# fishnet-0_1.net
KiCad netlist of a schematic drawn in EAGLE
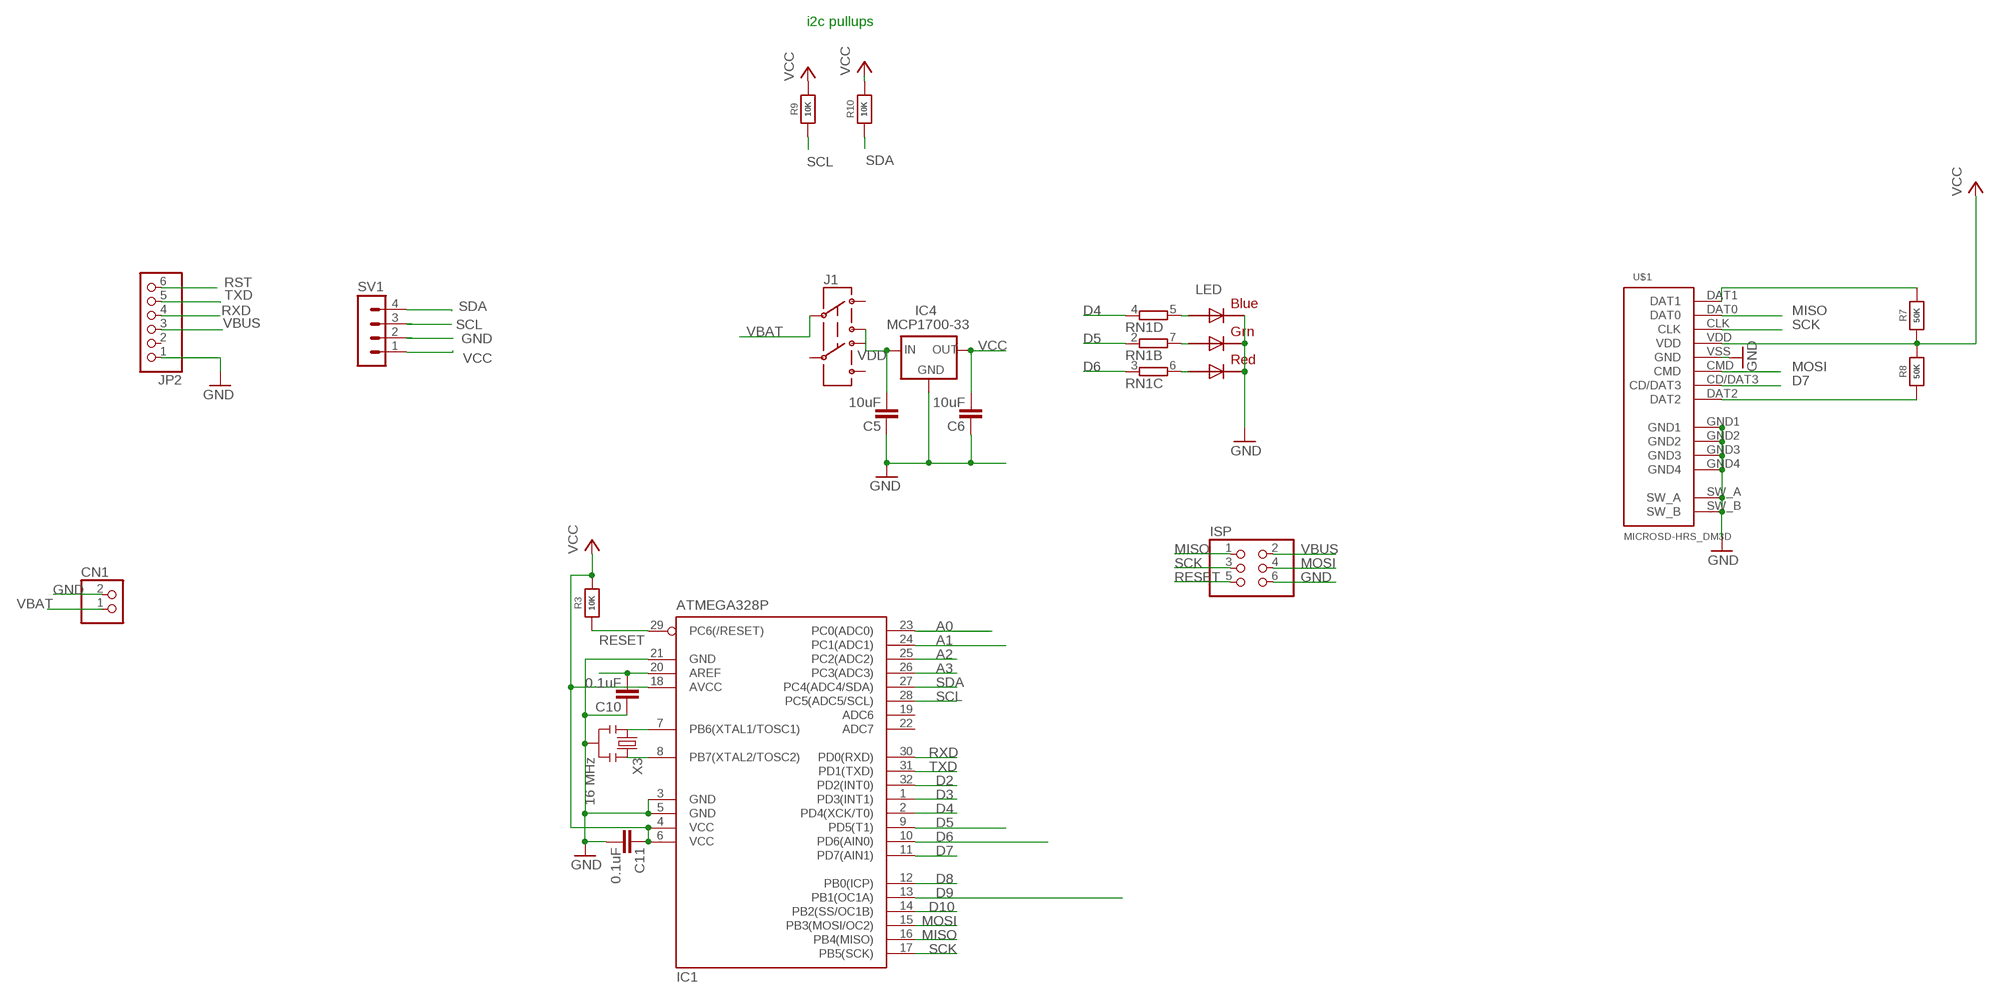
[diagram p0: schematic, sheet 1]

(export (version "E")
  (design (tool "Eeschema 10.0.6"))
  (components
    (comp (ref "C5")
      (value "10uF")
      (footprint "eagle-import:0603-CAP")
      (libsource (lib "eagle-import") (part "CAP0603-CAP"))
    )
    (comp (ref "C6")
      (value "10uF")
      (footprint "eagle-import:0603-CAP")
      (libsource (lib "eagle-import") (part "CAP0603-CAP"))
    )
    (comp (ref "C10")
      (value "0.1uF")
      (footprint "eagle-import:0603-CAP")
      (libsource (lib "eagle-import") (part "CAP0603-CAP"))
    )
    (comp (ref "C11")
      (value "0.1uF")
      (footprint "eagle-import:0603-CAP")
      (libsource (lib "eagle-import") (part "CAP0603-CAP"))
    )
    (comp (ref "CN1")
      (value "JST_2PIN-SMT-RA")
      (footprint "eagle-import:JST-PH-2-SMT-RA")
      (libsource (lib "eagle-import") (part "JST_2PIN-SMT-RA"))
    )
    (comp (ref "IC1")
      (value "ATMEGA328P")
      (footprint "eagle-import:TQFP32-08")
      (fields (field (name "MPN") "ATMEGA8-16AU"))
      (libsource (lib "eagle-import") (part "MEGA8-AI"))
    )
    (comp (ref "IC4")
      (value "MCP1700-33")
      (footprint "eagle-import:SOT89")
      (libsource (lib "eagle-import") (part "MCP1700SOT89"))
    )
    (comp (ref "ISP")
      (value "PINHD-2X3")
      (footprint "eagle-import:2X03")
      (libsource (lib "eagle-import") (part "PINHD-2X3"))
    )
    (comp (ref "J1")
      (value "AYZ0202")
      (footprint "eagle-import:AYZ0202")
      (libsource (lib "eagle-import") (part "AYZ0202"))
    )
    (comp (ref "JP2")
      (value "PINHD-1X6")
      (footprint "eagle-import:1X06")
      (libsource (lib "eagle-import") (part "PINHD-1X6"))
    )
    (comp (ref "LED")
      (value "RGBLED5050")
      (footprint "eagle-import:RGBLED5050")
      (libsource (lib "eagle-import") (part "RGBLED5050"))
    )
    (comp (ref "R3")
      (value "10K")
      (footprint "eagle-import:0603-NO")
      (libsource (lib "eagle-import") (part "RESISTOR_0603_NOOUT"))
    )
    (comp (ref "R7")
      (value "50K")
      (footprint "eagle-import:0603-NO")
      (libsource (lib "eagle-import") (part "RESISTOR_0603_NOOUT"))
    )
    (comp (ref "R8")
      (value "50K")
      (footprint "eagle-import:0603-NO")
      (libsource (lib "eagle-import") (part "RESISTOR_0603_NOOUT"))
    )
    (comp (ref "R9")
      (value "10K")
      (footprint "eagle-import:0603-NO")
      (libsource (lib "eagle-import") (part "RESISTOR_0603_NOOUT"))
    )
    (comp (ref "R10")
      (value "10K")
      (footprint "eagle-import:0603-NO")
      (libsource (lib "eagle-import") (part "RESISTOR_0603_NOOUT"))
    )
    (comp (ref "RN1")
      (value "4R-NEXB38V")
      (footprint "eagle-import:EXB38V")
      (libsource (lib "eagle-import") (part "4R-NEXB38V"))
    )
    (comp (ref "SV1")
      (value "MA04-1")
      (footprint "eagle-import:MA04-1")
      (libsource (lib "eagle-import") (part "MA04-1"))
    )
    (comp (ref "U$1")
      (value "MICROSD-HRS_DM3D")
      (footprint "eagle-import:DM3D")
      (libsource (lib "eagle-import") (part "MICROSD-HRS_DM3D"))
    )
    (comp (ref "X3")
      (value "16 MHz")
      (footprint "eagle-import:RESONATOR-SMD")
      (libsource (lib "eagle-import") (part "RESONATORSMD"))
    )
  )
  (nets
    (net (code "1") (name "/A0") (class "Default")
      (node (ref "IC1") (pin "23") (pinfunction "PC0(ADC0)_23") (pintype "bidirectional"))
    )
    (net (code "2") (name "/A1") (class "Default")
      (node (ref "IC1") (pin "24") (pinfunction "PC1(ADC1)_24") (pintype "bidirectional"))
    )
    (net (code "3") (name "/A2") (class "Default")
      (node (ref "IC1") (pin "25") (pinfunction "PC2(ADC2)_25") (pintype "bidirectional"))
    )
    (net (code "4") (name "/A3") (class "Default")
      (node (ref "IC1") (pin "26") (pinfunction "PC3(ADC3)_26") (pintype "bidirectional"))
    )
    (net (code "5") (name "/D2") (class "Default")
      (node (ref "IC1") (pin "32") (pinfunction "PD2(INT0)_32") (pintype "bidirectional"))
    )
    (net (code "6") (name "/D3") (class "Default")
      (node (ref "IC1") (pin "1") (pinfunction "PD3(INT1)_1") (pintype "bidirectional"))
    )
    (net (code "7") (name "/D4") (class "Default")
      (node (ref "IC1") (pin "2") (pinfunction "PD4(XCK/T0)_2") (pintype "bidirectional"))
      (node (ref "RN1") (pin "4") (pinfunction "1_4") (pintype "passive"))
    )
    (net (code "8") (name "/D5") (class "Default")
      (node (ref "IC1") (pin "9") (pinfunction "PD5(T1)_9") (pintype "bidirectional"))
      (node (ref "RN1") (pin "2") (pinfunction "1_2") (pintype "passive"))
    )
    (net (code "9") (name "/D6") (class "Default")
      (node (ref "IC1") (pin "10") (pinfunction "PD6(AIN0)_10") (pintype "bidirectional"))
      (node (ref "RN1") (pin "3") (pinfunction "1_3") (pintype "passive"))
    )
    (net (code "10") (name "/D7") (class "Default")
      (node (ref "IC1") (pin "11") (pinfunction "PD7(AIN1)_11") (pintype "bidirectional"))
      (node (ref "U$1") (pin "CD/DAT3") (pinfunction "CD/DAT3_CD/DAT3") (pintype "bidirectional"))
    )
    (net (code "11") (name "/D8") (class "Default")
      (node (ref "IC1") (pin "12") (pinfunction "PB0(ICP)_12") (pintype "bidirectional"))
    )
    (net (code "12") (name "/D9") (class "Default")
      (node (ref "IC1") (pin "13") (pinfunction "PB1(OC1A)_13") (pintype "bidirectional"))
    )
    (net (code "13") (name "/D10") (class "Default")
      (node (ref "IC1") (pin "14") (pinfunction "PB2(SS/OC1B)_14") (pintype "bidirectional"))
    )
    (net (code "14") (name "/MISO") (class "Default")
      (node (ref "IC1") (pin "16") (pinfunction "PB4(MISO)_16") (pintype "bidirectional"))
      (node (ref "ISP") (pin "1") (pinfunction "1_1") (pintype "passive"))
      (node (ref "U$1") (pin "DAT0") (pinfunction "DAT0_DAT0") (pintype "bidirectional"))
    )
    (net (code "15") (name "/MOSI") (class "Default")
      (node (ref "IC1") (pin "15") (pinfunction "PB3(MOSI/OC2)_15") (pintype "bidirectional"))
      (node (ref "ISP") (pin "4") (pinfunction "4_4") (pintype "passive"))
      (node (ref "U$1") (pin "CMD") (pinfunction "CMD_CMD") (pintype "bidirectional"))
    )
    (net (code "16") (name "/RESET") (class "Default")
      (node (ref "IC1") (pin "29") (pinfunction "PC6(/RESET)_29") (pintype "bidirectional"))
      (node (ref "ISP") (pin "5") (pinfunction "5_5") (pintype "passive"))
      (node (ref "R3") (pin "1") (pinfunction "1_1") (pintype "passive"))
    )
    (net (code "17") (name "/RST") (class "Default")
      (node (ref "JP2") (pin "6") (pinfunction "6_6") (pintype "passive"))
    )
    (net (code "18") (name "/RXD") (class "Default")
      (node (ref "IC1") (pin "30") (pinfunction "PD0(RXD)_30") (pintype "bidirectional"))
      (node (ref "JP2") (pin "4") (pinfunction "4_4") (pintype "passive"))
    )
    (net (code "19") (name "/SCK") (class "Default")
      (node (ref "IC1") (pin "17") (pinfunction "PB5(SCK)_17") (pintype "bidirectional"))
      (node (ref "ISP") (pin "3") (pinfunction "3_3") (pintype "passive"))
      (node (ref "U$1") (pin "CLK") (pinfunction "CLK_CLK") (pintype "bidirectional"))
    )
    (net (code "20") (name "/SCL") (class "Default")
      (node (ref "IC1") (pin "28") (pinfunction "PC5(ADC5/SCL)_28") (pintype "bidirectional"))
      (node (ref "R9") (pin "1") (pinfunction "1_1") (pintype "passive"))
      (node (ref "SV1") (pin "3") (pinfunction "3_3") (pintype "passive"))
    )
    (net (code "21") (name "/SDA") (class "Default")
      (node (ref "IC1") (pin "27") (pinfunction "PC4(ADC4/SDA)_27") (pintype "bidirectional"))
      (node (ref "R10") (pin "1") (pinfunction "1_1") (pintype "passive"))
      (node (ref "SV1") (pin "4") (pinfunction "4_4") (pintype "passive"))
    )
    (net (code "22") (name "/TXD") (class "Default")
      (node (ref "IC1") (pin "31") (pinfunction "PD1(TXD)_31") (pintype "bidirectional"))
      (node (ref "JP2") (pin "5") (pinfunction "5_5") (pintype "passive"))
    )
    (net (code "23") (name "/VBAT") (class "Default")
      (node (ref "CN1") (pin "1") (pinfunction "2_1") (pintype "passive"))
      (node (ref "J1") (pin "2") (pinfunction "2_2") (pintype "bidirectional"))
    )
    (net (code "24") (name "/VBUS") (class "Default")
      (node (ref "ISP") (pin "2") (pinfunction "2_2") (pintype "passive"))
      (node (ref "JP2") (pin "3") (pinfunction "3_3") (pintype "passive"))
    )
    (net (code "25") (name "/VDD") (class "Default")
      (node (ref "C5") (pin "1") (pinfunction "1_1") (pintype "passive"))
      (node (ref "IC4") (pin "2") (pinfunction "IN_2") (pintype "input"))
      (node (ref "J1") (pin "1") (pinfunction "3_1") (pintype "bidirectional"))
    )
    (net (code "26") (name "GND") (class "Default")
      (node (ref "C10") (pin "2") (pinfunction "2_2") (pintype "passive"))
      (node (ref "C11") (pin "1") (pinfunction "1_1") (pintype "passive"))
      (node (ref "C5") (pin "2") (pinfunction "2_2") (pintype "passive"))
      (node (ref "C6") (pin "2") (pinfunction "2_2") (pintype "passive"))
      (node (ref "CN1") (pin "2") (pinfunction "1_2") (pintype "passive"))
      (node (ref "IC1") (pin "21") (pinfunction "GND_21") (pintype "power_in"))
      (node (ref "IC1") (pin "3") (pinfunction "GND_3") (pintype "power_in"))
      (node (ref "IC1") (pin "5") (pinfunction "GND_5") (pintype "power_in"))
      (node (ref "IC4") (pin "1") (pinfunction "GND_1") (pintype "input"))
      (node (ref "ISP") (pin "6") (pinfunction "6_6") (pintype "passive"))
      (node (ref "JP2") (pin "1") (pinfunction "1_1") (pintype "passive"))
      (node (ref "LED") (pin "4") (pinfunction "BLUE_C_4") (pintype "bidirectional"))
      (node (ref "LED") (pin "5") (pinfunction "RED_C_5") (pintype "bidirectional"))
      (node (ref "LED") (pin "6") (pinfunction "GREEN_C_6") (pintype "bidirectional"))
      (node (ref "SV1") (pin "2") (pinfunction "2_2") (pintype "passive"))
      (node (ref "U$1") (pin "GND1") (pinfunction "GND1_GND1") (pintype "bidirectional"))
      (node (ref "U$1") (pin "GND2") (pinfunction "GND2_GND2") (pintype "bidirectional"))
      (node (ref "U$1") (pin "GND3") (pinfunction "GND3_GND3") (pintype "bidirectional"))
      (node (ref "U$1") (pin "GND4") (pinfunction "GND4_GND4") (pintype "bidirectional"))
      (node (ref "U$1") (pin "SW_A") (pinfunction "SW_A_SW_A") (pintype "bidirectional"))
      (node (ref "U$1") (pin "SW_B") (pinfunction "SW_B_SW_B") (pintype "bidirectional"))
      (node (ref "U$1") (pin "VSS") (pinfunction "GND_VSS") (pintype "bidirectional"))
      (node (ref "X3") (pin "2") (pinfunction "2_2") (pintype "passive"))
    )
    (net (code "27") (name "Net-(IC1-AREF)") (class "Default")
      (node (ref "C10") (pin "1") (pinfunction "1_1") (pintype "passive"))
      (node (ref "IC1") (pin "20") (pinfunction "AREF_20") (pintype "passive"))
    )
    (net (code "28") (name "Net-(IC1-PB6(XTAL1{slash}TOSC1))") (class "Default")
      (node (ref "IC1") (pin "7") (pinfunction "PB6(XTAL1/TOSC1)_7") (pintype "bidirectional"))
      (node (ref "X3") (pin "1") (pinfunction "1_1") (pintype "passive"))
    )
    (net (code "29") (name "Net-(IC1-PB7(XTAL2{slash}TOSC2))") (class "Default")
      (node (ref "IC1") (pin "8") (pinfunction "PB7(XTAL2/TOSC2)_8") (pintype "bidirectional"))
      (node (ref "X3") (pin "3") (pinfunction "3_3") (pintype "passive"))
    )
    (net (code "30") (name "Net-(LED-BLUE_A)") (class "Default")
      (node (ref "LED") (pin "3") (pinfunction "BLUE_A_3") (pintype "bidirectional"))
      (node (ref "RN1") (pin "5") (pinfunction "2_5") (pintype "passive"))
    )
    (net (code "31") (name "Net-(LED-GREEN_A)") (class "Default")
      (node (ref "LED") (pin "1") (pinfunction "GREEN_A_1") (pintype "bidirectional"))
      (node (ref "RN1") (pin "7") (pinfunction "2_7") (pintype "passive"))
    )
    (net (code "32") (name "Net-(LED-RED_A)") (class "Default")
      (node (ref "LED") (pin "2") (pinfunction "RED_A_2") (pintype "bidirectional"))
      (node (ref "RN1") (pin "6") (pinfunction "2_6") (pintype "passive"))
    )
    (net (code "33") (name "Net-(R7-Pad2)") (class "Default")
      (node (ref "R7") (pin "2") (pinfunction "2_2") (pintype "passive"))
      (node (ref "U$1") (pin "DAT1") (pinfunction "DAT1_DAT1") (pintype "bidirectional"))
    )
    (net (code "34") (name "Net-(R8-Pad1)") (class "Default")
      (node (ref "R8") (pin "1") (pinfunction "1_1") (pintype "passive"))
      (node (ref "U$1") (pin "DAT2") (pinfunction "DAT2_DAT2") (pintype "bidirectional"))
    )
    (net (code "35") (name "VCC") (class "Default")
      (node (ref "C11") (pin "2") (pinfunction "2_2") (pintype "passive"))
      (node (ref "C6") (pin "1") (pinfunction "1_1") (pintype "passive"))
      (node (ref "IC1") (pin "18") (pinfunction "AVCC_18") (pintype "power_in"))
      (node (ref "IC1") (pin "4") (pinfunction "VCC_4") (pintype "power_in"))
      (node (ref "IC1") (pin "6") (pinfunction "VCC_6") (pintype "power_in"))
      (node (ref "IC4") (pin "3") (pinfunction "OUT_3") (pintype "passive"))
      (node (ref "R10") (pin "2") (pinfunction "2_2") (pintype "passive"))
      (node (ref "R3") (pin "2") (pinfunction "2_2") (pintype "passive"))
      (node (ref "R7") (pin "1") (pinfunction "1_1") (pintype "passive"))
      (node (ref "R8") (pin "2") (pinfunction "2_2") (pintype "passive"))
      (node (ref "R9") (pin "2") (pinfunction "2_2") (pintype "passive"))
      (node (ref "SV1") (pin "1") (pinfunction "1_1") (pintype "passive"))
      (node (ref "U$1") (pin "VDD") (pinfunction "VDD_VDD") (pintype "bidirectional"))
    )
    (net (code "36") (name "unconnected-(IC1-ADC6-Pad19)") (class "Default")
      (node (ref "IC1") (pin "19") (pinfunction "ADC6_19") (pintype "bidirectional"))
    )
    (net (code "37") (name "unconnected-(IC1-ADC7-Pad22)") (class "Default")
      (node (ref "IC1") (pin "22") (pinfunction "ADC7_22") (pintype "bidirectional"))
    )
    (net (code "38") (name "unconnected-(J1-1-Pad3)") (class "Default")
      (node (ref "J1") (pin "3") (pinfunction "1_3") (pintype "bidirectional"))
    )
    (net (code "39") (name "unconnected-(J1-4-Pad6)") (class "Default")
      (node (ref "J1") (pin "6") (pinfunction "4_6") (pintype "bidirectional"))
    )
    (net (code "40") (name "unconnected-(J1-6-Pad4)") (class "Default")
      (node (ref "J1") (pin "4") (pinfunction "6_4") (pintype "bidirectional"))
    )
    (net (code "41") (name "unconnected-(J1-Pad5)") (class "Default")
      (node (ref "J1") (pin "5") (pinfunction "5_5") (pintype "bidirectional"))
    )
    (net (code "42") (name "unconnected-(JP2-Pad2)") (class "Default")
      (node (ref "JP2") (pin "2") (pinfunction "2_2") (pintype "passive"))
    )
  )
)
